# 1-Schematic_New_Projec.net
KiCad netlist of a schematic drawn in EasyEDA
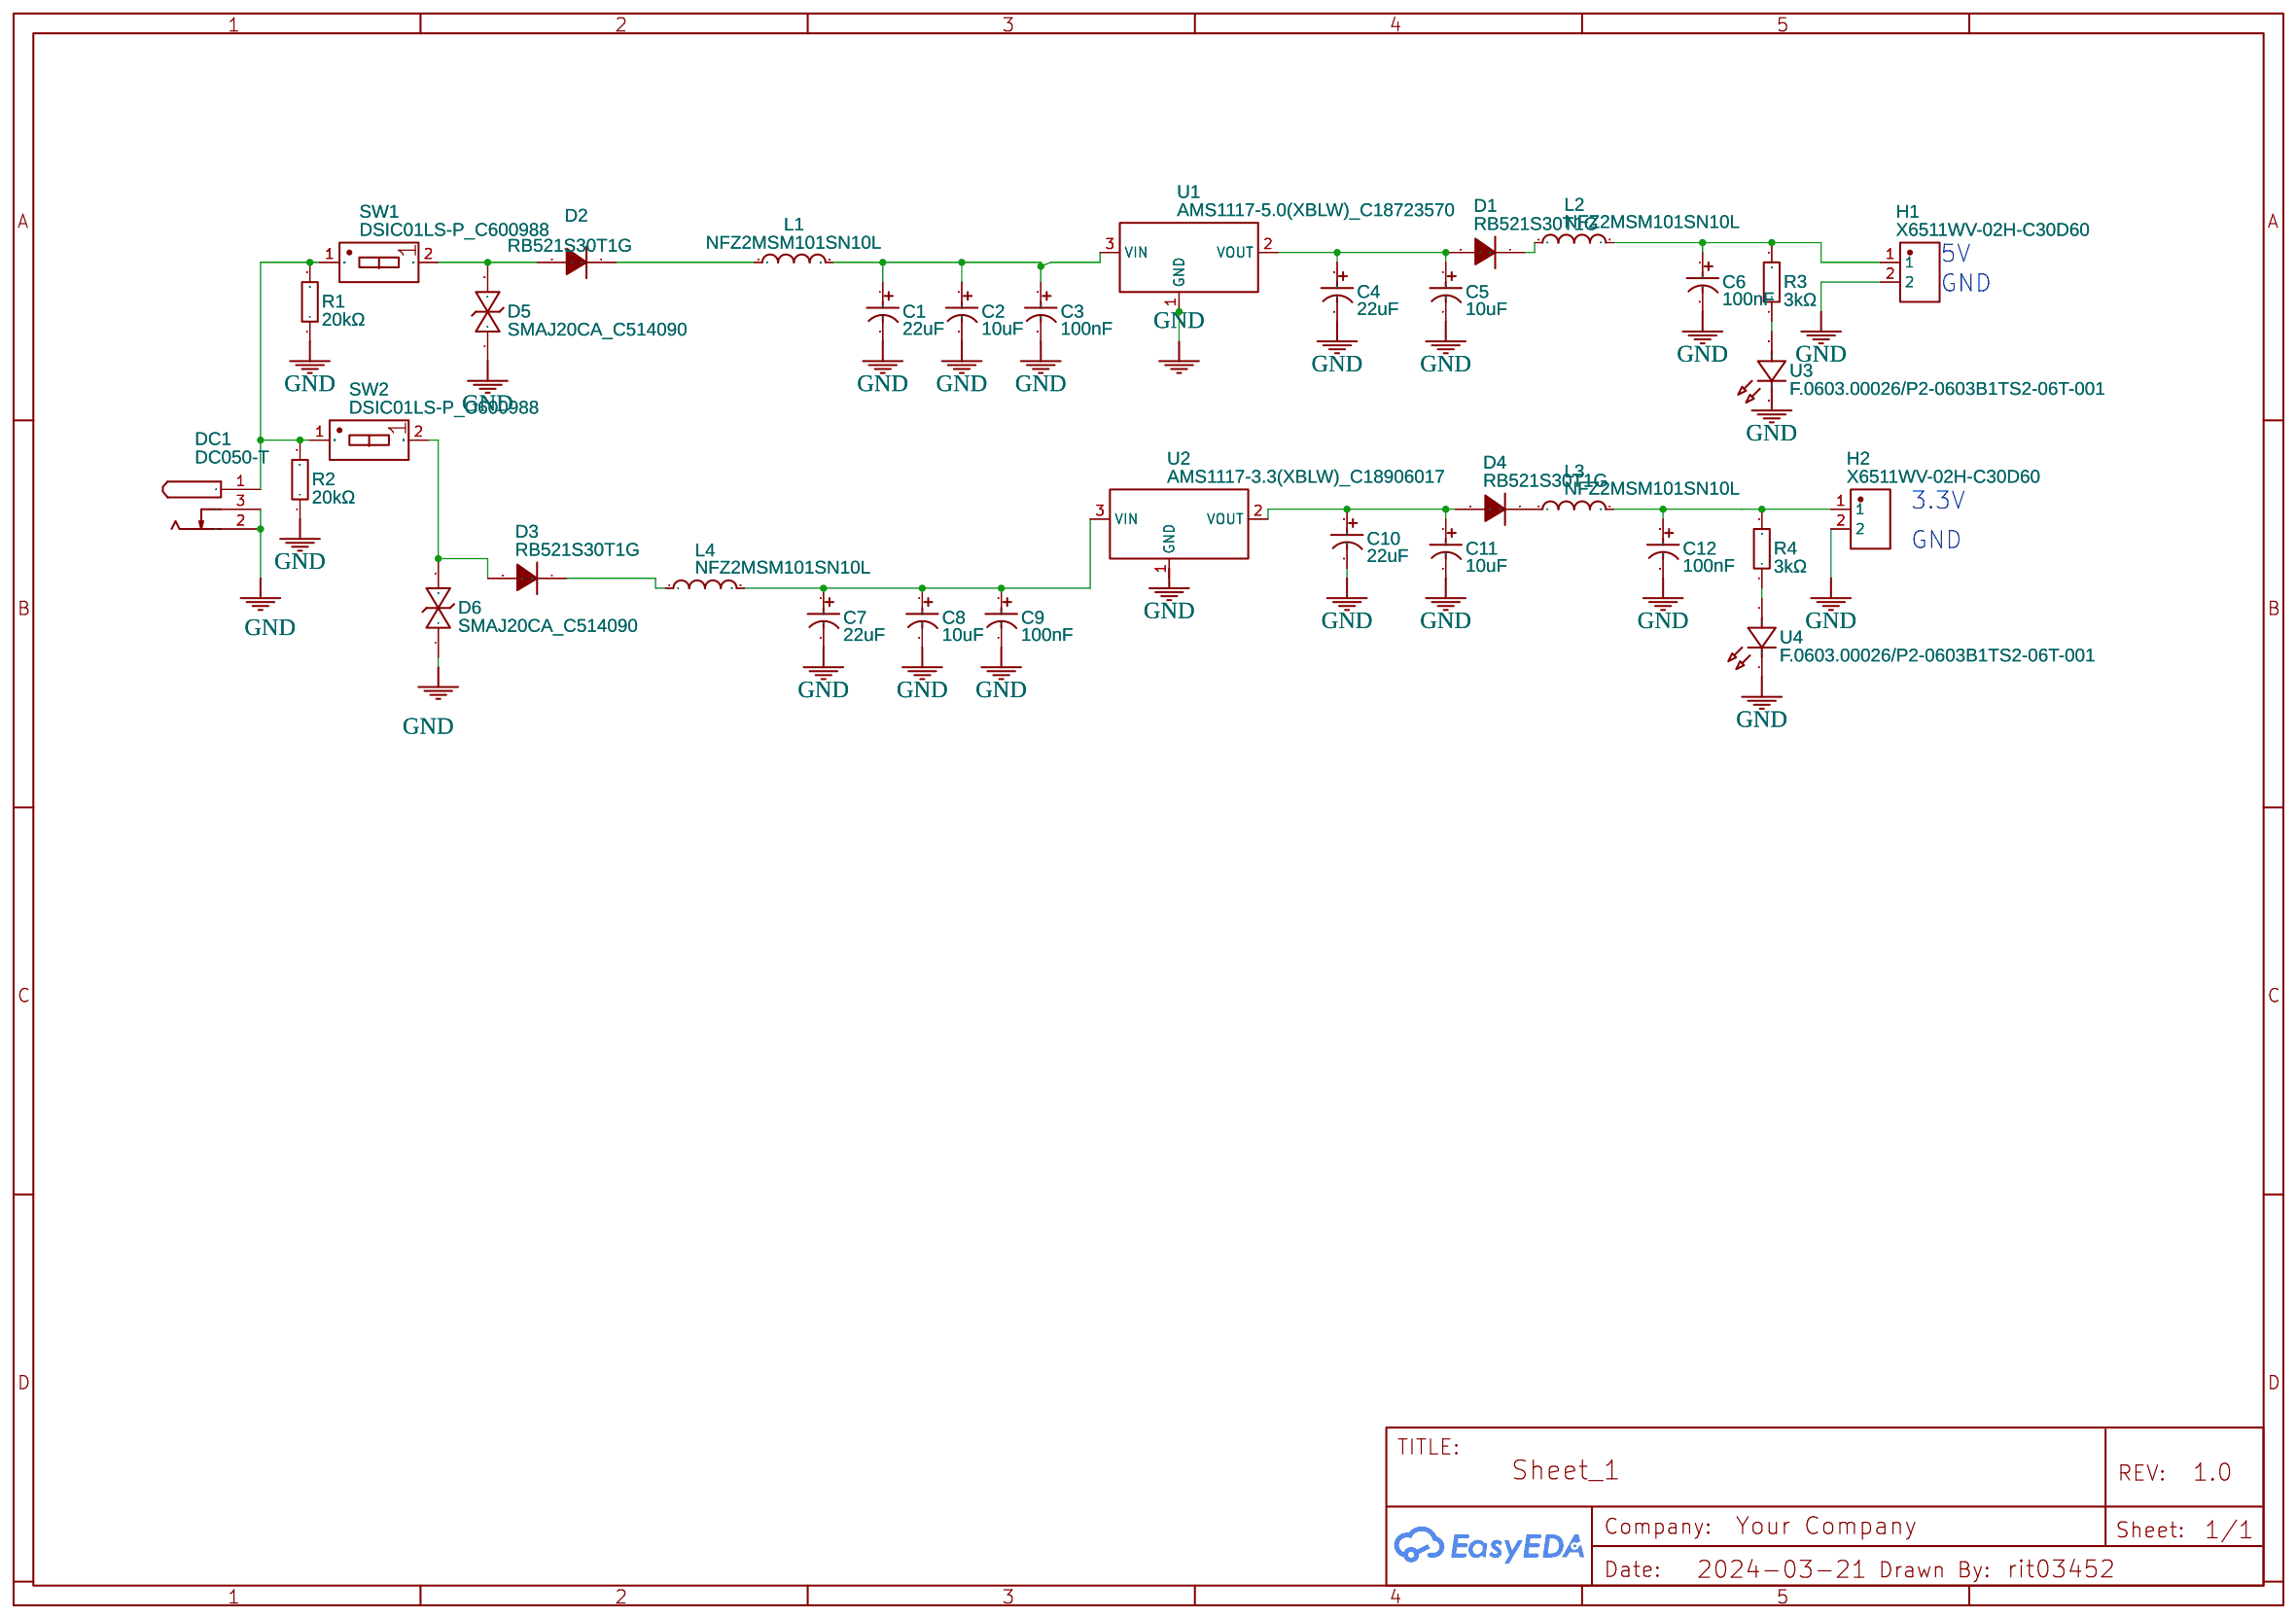
[diagram p0: schematic sheet]

(export (version "E")
  (design (tool "Eeschema 10.0.6"))
  (components
    (comp (ref "C1")
      (value "22uF")
      (fields
        (field (name "Manufacturer Part") "KM226M050D11RR0VH2FP0")
        (field (name "Manufacturer") "CX(承兴)")
      )
      (libsource (lib "") (part "22uF 50V 5*11"))
    )
    (comp (ref "C2")
      (value "10uF")
      (fields
        (field (name "Manufacturer Part") "KM106M050D11RR0VH2FP0")
        (field (name "Manufacturer") "CX(承兴)")
      )
      (libsource (lib "") (part "10uF 50V 5*11"))
    )
    (comp (ref "C3")
      (value "100nF")
      (fields
        (field (name "Manufacturer Part") "KM104M050D11RR0VH2FP0")
        (field (name "Manufacturer") "CX(承兴)")
      )
      (libsource (lib "") (part "0.1UF 50V"))
    )
    (comp (ref "C4")
      (value "22uF")
      (fields
        (field (name "Manufacturer Part") "KM226M050D11RR0VH2FP0")
        (field (name "Manufacturer") "CX(承兴)")
      )
      (libsource (lib "") (part "22uF 50V 5*11"))
    )
    (comp (ref "C5")
      (value "10uF")
      (fields
        (field (name "Manufacturer Part") "KM106M050D11RR0VH2FP0")
        (field (name "Manufacturer") "CX(承兴)")
      )
      (libsource (lib "") (part "10uF 50V 5*11"))
    )
    (comp (ref "C6")
      (value "100nF")
      (fields
        (field (name "Manufacturer Part") "KM104M050D11RR0VH2FP0")
        (field (name "Manufacturer") "CX(承兴)")
      )
      (libsource (lib "") (part "0.1UF 50V"))
    )
    (comp (ref "C7")
      (value "22uF")
      (fields
        (field (name "Manufacturer Part") "KM226M050D11RR0VH2FP0")
        (field (name "Manufacturer") "CX(承兴)")
      )
      (libsource (lib "") (part "22uF 50V 5*11"))
    )
    (comp (ref "C8")
      (value "10uF")
      (fields
        (field (name "Manufacturer Part") "KM106M050D11RR0VH2FP0")
        (field (name "Manufacturer") "CX(承兴)")
      )
      (libsource (lib "") (part "10uF 50V 5*11"))
    )
    (comp (ref "C9")
      (value "100nF")
      (fields
        (field (name "Manufacturer Part") "KM104M050D11RR0VH2FP0")
        (field (name "Manufacturer") "CX(承兴)")
      )
      (libsource (lib "") (part "0.1UF 50V"))
    )
    (comp (ref "C10")
      (value "22uF")
      (fields
        (field (name "Manufacturer Part") "KM226M050D11RR0VH2FP0")
        (field (name "Manufacturer") "CX(承兴)")
      )
      (libsource (lib "") (part "22uF 50V 5*11"))
    )
    (comp (ref "C11")
      (value "10uF")
      (fields
        (field (name "Manufacturer Part") "KM106M050D11RR0VH2FP0")
        (field (name "Manufacturer") "CX(承兴)")
      )
      (libsource (lib "") (part "10uF 50V 5*11"))
    )
    (comp (ref "C12")
      (value "100nF")
      (fields
        (field (name "Manufacturer Part") "KM104M050D11RR0VH2FP0")
        (field (name "Manufacturer") "CX(承兴)")
      )
      (libsource (lib "") (part "0.1UF 50V"))
    )
    (comp (ref "D1")
      (value "RB521S30T1G")
      (fields (field (name "Manufacturer") "onsemi(安森美)"))
      (libsource (lib "") (part "RB521S30T1G"))
    )
    (comp (ref "D2")
      (value "RB521S30T1G")
      (fields (field (name "Manufacturer") "onsemi(安森美)"))
      (libsource (lib "") (part "RB521S30T1G"))
    )
    (comp (ref "D3")
      (value "RB521S30T1G")
      (fields (field (name "Manufacturer") "onsemi(安森美)"))
      (libsource (lib "") (part "RB521S30T1G"))
    )
    (comp (ref "D4")
      (value "RB521S30T1G")
      (fields (field (name "Manufacturer") "onsemi(安森美)"))
      (libsource (lib "") (part "RB521S30T1G"))
    )
    (comp (ref "D5")
      (value "SMAJ20CA_C514090")
      (fields (field (name "Manufacturer Part") "SMAJ20CA") (field (name "Manufacturer") "High Diode(海德)"))
      (libsource (lib "") (part "SMAJ20CA_C514090"))
    )
    (comp (ref "D6")
      (value "SMAJ20CA_C514090")
      (fields (field (name "Manufacturer Part") "SMAJ20CA") (field (name "Manufacturer") "High Diode(海德)"))
      (libsource (lib "") (part "SMAJ20CA_C514090"))
    )
    (comp (ref "DC1")
      (value "DC050-T")
      (fields (field (name "Manufacturer") "SHOU HAN(首韩)"))
      (libsource (lib "") (part "DC050-T"))
    )
    (comp (ref "H1")
      (value "X6511WV-02H-C30D60")
      (fields
        (field (name "Manufacturer Part") "X6511WV-02H-C60D30")
        (field (name "Manufacturer") "XKB Connection(中国星坤)")
      )
      (libsource (lib "") (part "X6511WV-02H-C30D60"))
    )
    (comp (ref "H2")
      (value "X6511WV-02H-C30D60")
      (fields
        (field (name "Manufacturer Part") "X6511WV-02H-C60D30")
        (field (name "Manufacturer") "XKB Connection(中国星坤)")
      )
      (libsource (lib "") (part "X6511WV-02H-C30D60"))
    )
    (comp (ref "L1")
      (value "NFZ2MSM101SN10L")
      (fields (field (name "Manufacturer") "muRata(村田)"))
      (libsource (lib "") (part "NFZ2MSM101SN10L"))
    )
    (comp (ref "L2")
      (value "NFZ2MSM101SN10L")
      (fields (field (name "Manufacturer") "muRata(村田)"))
      (libsource (lib "") (part "NFZ2MSM101SN10L"))
    )
    (comp (ref "L3")
      (value "NFZ2MSM101SN10L")
      (fields (field (name "Manufacturer") "muRata(村田)"))
      (libsource (lib "") (part "NFZ2MSM101SN10L"))
    )
    (comp (ref "L4")
      (value "NFZ2MSM101SN10L")
      (fields (field (name "Manufacturer") "muRata(村田)"))
      (libsource (lib "") (part "NFZ2MSM101SN10L"))
    )
    (comp (ref "R1")
      (value "20kΩ")
      (fields
        (field (name "Manufacturer Part") "0603WAF2002T5E")
        (field (name "Manufacturer") "UNI-ROYAL(厚声)")
      )
      (libsource (lib "") (part "0603WAF2002T5E"))
    )
    (comp (ref "R2")
      (value "20kΩ")
      (fields
        (field (name "Manufacturer Part") "0603WAF2002T5E")
        (field (name "Manufacturer") "UNI-ROYAL(厚声)")
      )
      (libsource (lib "") (part "0603WAF2002T5E"))
    )
    (comp (ref "R3")
      (value "3kΩ")
      (fields
        (field (name "Manufacturer Part") "0402WGF3001TCE")
        (field (name "Manufacturer") "UNI-ROYAL(厚声)")
      )
      (libsource (lib "") (part "0402WGF3001TCE"))
    )
    (comp (ref "R4")
      (value "3kΩ")
      (fields
        (field (name "Manufacturer Part") "0402WGF3001TCE")
        (field (name "Manufacturer") "UNI-ROYAL(厚声)")
      )
      (libsource (lib "") (part "0402WGF3001TCE"))
    )
    (comp (ref "SW1")
      (value "DSIC01LS-P_C600988")
      (fields
        (field (name "Manufacturer Part") "DSIC01LS-P")
        (field (name "Manufacturer") "XKB Connectivity(中国星坤)")
      )
      (libsource (lib "") (part "DSIC01LS-P_C600988"))
    )
    (comp (ref "SW2")
      (value "DSIC01LS-P_C600988")
      (fields
        (field (name "Manufacturer Part") "DSIC01LS-P")
        (field (name "Manufacturer") "XKB Connectivity(中国星坤)")
      )
      (libsource (lib "") (part "DSIC01LS-P_C600988"))
    )
    (comp (ref "U1")
      (value "AMS1117-5.0(XBLW)_C18723570")
      (fields
        (field (name "Manufacturer Part") "AMS1117-5.0(XBLW)")
        (field (name "Manufacturer") "XBLW(芯伯乐)")
      )
      (libsource (lib "") (part "AMS1117-5.0(XBLW)_C18723570"))
    )
    (comp (ref "U2")
      (value "AMS1117-3.3(XBLW)_C18906017")
      (fields
        (field (name "Manufacturer Part") "AMS1117-3.3(XBLW)")
        (field (name "Manufacturer") "XBLW(芯伯乐)")
      )
      (libsource (lib "") (part "AMS1117-3.3(XBLW)_C18906017"))
    )
    (comp (ref "U3")
      (value "F.0603.00026/P2-0603B1TS2-06T-001")
      (fields (field (name "Manufacturer") "TUOZHAN(拓展光电)"))
      (libsource (lib "") (part "F.0603.00026/P2-0603B1TS2-06T-001"))
    )
    (comp (ref "U4")
      (value "F.0603.00026/P2-0603B1TS2-06T-001")
      (fields (field (name "Manufacturer") "TUOZHAN(拓展光电)"))
      (libsource (lib "") (part "F.0603.00026/P2-0603B1TS2-06T-001"))
    )
  )
  (nets
    (net (code "1") (name "GND") (class "Default")
      (node (ref "C1") (pin "2") (pinfunction "2_2") (pintype "input"))
      (node (ref "C10") (pin "2") (pinfunction "2_2") (pintype "input"))
      (node (ref "C11") (pin "2") (pinfunction "2_2") (pintype "input"))
      (node (ref "C12") (pin "2") (pinfunction "2_2") (pintype "input"))
      (node (ref "C2") (pin "2") (pinfunction "2_2") (pintype "input"))
      (node (ref "C3") (pin "2") (pinfunction "2_2") (pintype "input"))
      (node (ref "C4") (pin "2") (pinfunction "2_2") (pintype "input"))
      (node (ref "C5") (pin "2") (pinfunction "2_2") (pintype "input"))
      (node (ref "C6") (pin "2") (pinfunction "2_2") (pintype "input"))
      (node (ref "C7") (pin "2") (pinfunction "2_2") (pintype "input"))
      (node (ref "C8") (pin "2") (pinfunction "2_2") (pintype "input"))
      (node (ref "C9") (pin "2") (pinfunction "2_2") (pintype "input"))
      (node (ref "D5") (pin "1") (pinfunction "1_1") (pintype "unspecified"))
      (node (ref "D6") (pin "1") (pinfunction "1_1") (pintype "unspecified"))
      (node (ref "DC1") (pin "2") (pinfunction "2_2") (pintype "unspecified"))
      (node (ref "DC1") (pin "3") (pinfunction "3_3") (pintype "unspecified"))
      (node (ref "H1") (pin "2") (pinfunction "2_2") (pintype "unspecified"))
      (node (ref "H2") (pin "2") (pinfunction "2_2") (pintype "unspecified"))
      (node (ref "R1") (pin "1") (pinfunction "1_1") (pintype "input"))
      (node (ref "R2") (pin "1") (pinfunction "1_1") (pintype "input"))
      (node (ref "U1") (pin "1") (pinfunction "GND_1") (pintype "unspecified"))
      (node (ref "U2") (pin "1") (pinfunction "GND_1") (pintype "unspecified"))
      (node (ref "U3") (pin "1") (pinfunction "K_1") (pintype "unspecified"))
      (node (ref "U4") (pin "1") (pinfunction "K_1") (pintype "unspecified"))
    )
    (net (code "2") (name "Net-(C6-Pad1)") (class "Default")
      (node (ref "C6") (pin "1") (pinfunction "1_1") (pintype "input"))
      (node (ref "H1") (pin "1") (pinfunction "1_1") (pintype "unspecified"))
      (node (ref "L2") (pin "2") (pinfunction "2_2") (pintype "unspecified"))
      (node (ref "R3") (pin "2") (pinfunction "2_2") (pintype "input"))
    )
    (net (code "3") (name "Net-(C12-Pad1)") (class "Default")
      (node (ref "C12") (pin "1") (pinfunction "1_1") (pintype "input"))
      (node (ref "H2") (pin "1") (pinfunction "1_1") (pintype "unspecified"))
      (node (ref "L3") (pin "2") (pinfunction "2_2") (pintype "unspecified"))
      (node (ref "R4") (pin "2") (pinfunction "2_2") (pintype "input"))
    )
    (net (code "4") (name "Net-(D1-A)") (class "Default")
      (node (ref "C4") (pin "1") (pinfunction "1_1") (pintype "input"))
      (node (ref "C5") (pin "1") (pinfunction "1_1") (pintype "input"))
      (node (ref "D1") (pin "2") (pinfunction "A_2") (pintype "unspecified"))
      (node (ref "U1") (pin "2") (pinfunction "VOUT_2") (pintype "unspecified"))
    )
    (net (code "5") (name "Net-(D1-C)") (class "Default")
      (node (ref "D1") (pin "1") (pinfunction "C_1") (pintype "unspecified"))
      (node (ref "L2") (pin "1") (pinfunction "1_1") (pintype "unspecified"))
    )
    (net (code "6") (name "Net-(D2-A)") (class "Default")
      (node (ref "D2") (pin "2") (pinfunction "A_2") (pintype "unspecified"))
      (node (ref "D5") (pin "2") (pinfunction "2_2") (pintype "unspecified"))
      (node (ref "SW1") (pin "2") (pinfunction "PIN2_2") (pintype "unspecified"))
    )
    (net (code "7") (name "Net-(D2-C)") (class "Default")
      (node (ref "D2") (pin "1") (pinfunction "C_1") (pintype "unspecified"))
      (node (ref "L1") (pin "1") (pinfunction "1_1") (pintype "unspecified"))
    )
    (net (code "8") (name "Net-(D3-A)") (class "Default")
      (node (ref "D3") (pin "2") (pinfunction "A_2") (pintype "unspecified"))
      (node (ref "D6") (pin "2") (pinfunction "2_2") (pintype "unspecified"))
      (node (ref "SW2") (pin "2") (pinfunction "PIN2_2") (pintype "unspecified"))
    )
    (net (code "9") (name "Net-(D3-C)") (class "Default")
      (node (ref "D3") (pin "1") (pinfunction "C_1") (pintype "unspecified"))
      (node (ref "L4") (pin "1") (pinfunction "1_1") (pintype "unspecified"))
    )
    (net (code "10") (name "Net-(D4-A)") (class "Default")
      (node (ref "C10") (pin "1") (pinfunction "1_1") (pintype "input"))
      (node (ref "C11") (pin "1") (pinfunction "1_1") (pintype "input"))
      (node (ref "D4") (pin "2") (pinfunction "A_2") (pintype "unspecified"))
      (node (ref "U2") (pin "2") (pinfunction "VOUT_2") (pintype "unspecified"))
    )
    (net (code "11") (name "Net-(D4-C)") (class "Default")
      (node (ref "D4") (pin "1") (pinfunction "C_1") (pintype "unspecified"))
      (node (ref "L3") (pin "1") (pinfunction "1_1") (pintype "unspecified"))
    )
    (net (code "12") (name "Net-(SW1-PIN1)") (class "Default")
      (node (ref "DC1") (pin "1") (pinfunction "1_1") (pintype "unspecified"))
      (node (ref "R1") (pin "2") (pinfunction "2_2") (pintype "input"))
      (node (ref "R2") (pin "2") (pinfunction "2_2") (pintype "input"))
      (node (ref "SW1") (pin "1") (pinfunction "PIN1_1") (pintype "unspecified"))
      (node (ref "SW2") (pin "1") (pinfunction "PIN1_1") (pintype "unspecified"))
    )
    (net (code "13") (name "Net-(U1-VIN)") (class "Default")
      (node (ref "C1") (pin "1") (pinfunction "1_1") (pintype "input"))
      (node (ref "C2") (pin "1") (pinfunction "1_1") (pintype "input"))
      (node (ref "C3") (pin "1") (pinfunction "1_1") (pintype "input"))
      (node (ref "L1") (pin "2") (pinfunction "2_2") (pintype "unspecified"))
      (node (ref "U1") (pin "3") (pinfunction "VIN_3") (pintype "unspecified"))
    )
    (net (code "14") (name "Net-(U2-VIN)") (class "Default")
      (node (ref "C7") (pin "1") (pinfunction "1_1") (pintype "input"))
      (node (ref "C8") (pin "1") (pinfunction "1_1") (pintype "input"))
      (node (ref "C9") (pin "1") (pinfunction "1_1") (pintype "input"))
      (node (ref "L4") (pin "2") (pinfunction "2_2") (pintype "unspecified"))
      (node (ref "U2") (pin "3") (pinfunction "VIN_3") (pintype "unspecified"))
    )
    (net (code "15") (name "Net-(U3-A)") (class "Default")
      (node (ref "R3") (pin "1") (pinfunction "1_1") (pintype "input"))
      (node (ref "U3") (pin "2") (pinfunction "A_2") (pintype "unspecified"))
    )
    (net (code "16") (name "Net-(U4-A)") (class "Default")
      (node (ref "R4") (pin "1") (pinfunction "1_1") (pintype "input"))
      (node (ref "U4") (pin "2") (pinfunction "A_2") (pintype "unspecified"))
    )
  )
)
